# LOCO-WIFI.net
KiCad netlist of a schematic drawn in EAGLE
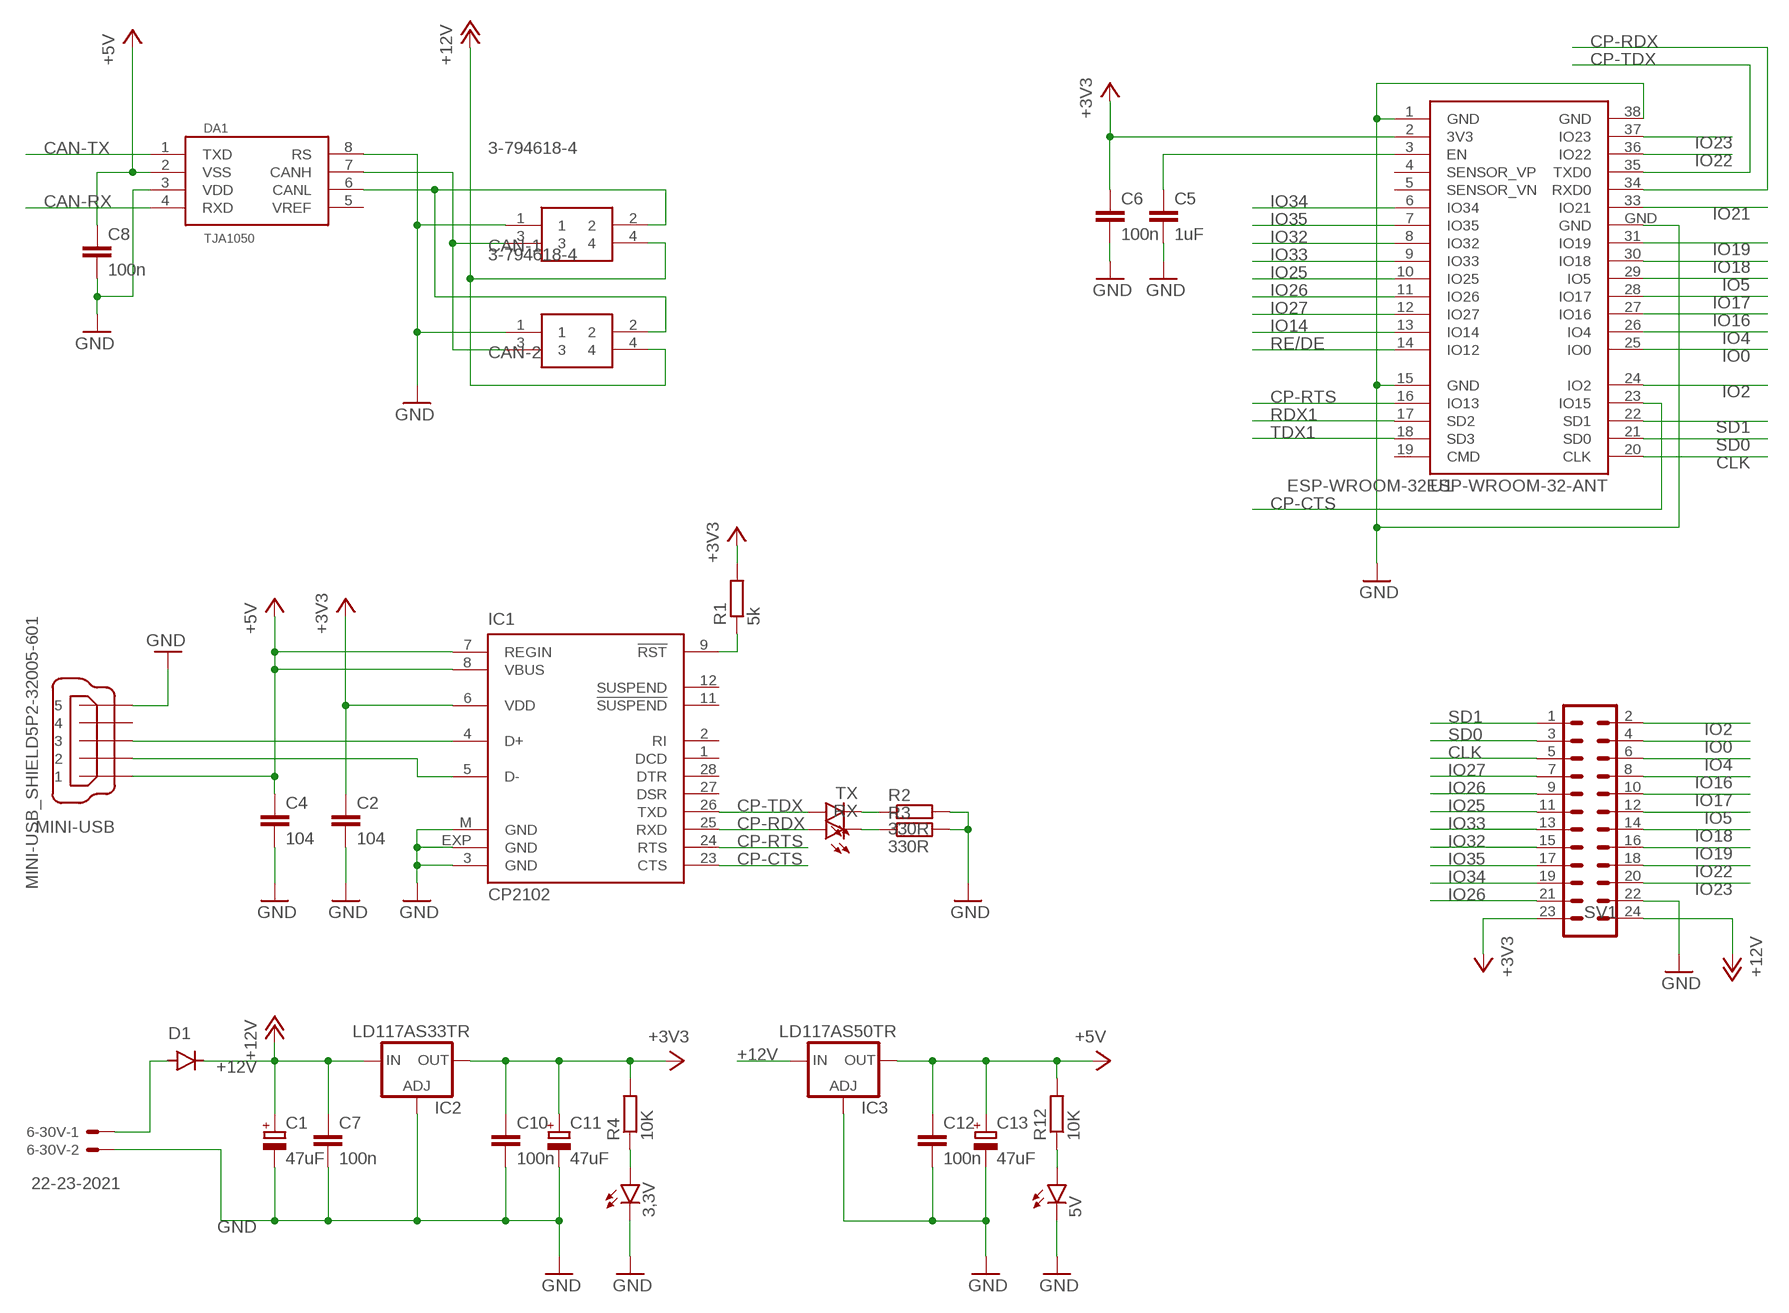
[diagram p0: schematic, sheet 1]

(export (version "E")
  (design (tool "Eeschema 10.0.6"))
  (components
    (comp (ref "3,3V")
      (value "LEDCHIPLED_0603")
      (footprint "eagle-import:CHIPLED_0603")
      (libsource (lib "eagle-import") (part "LEDCHIPLED_0603"))
    )
    (comp (ref "5V")
      (value "LEDCHIPLED_0603")
      (footprint "eagle-import:CHIPLED_0603")
      (libsource (lib "eagle-import") (part "LEDCHIPLED_0603"))
    )
    (comp (ref "6-30V")
      (value "22-23-2021")
      (footprint "eagle-import:22-23-2021")
      (fields (field (name "MF") "MOLEX"))
      (libsource (lib "eagle-import") (part "22-23-2021"))
    )
    (comp (ref "C1")
      (value "47uF")
      (footprint "eagle-import:B_3528-21R")
      (libsource (lib "eagle-import") (part "CPOL-EUB/3528-21R"))
    )
    (comp (ref "C2")
      (value "104")
      (footprint "eagle-import:C0402")
      (libsource (lib "eagle-import") (part "C-EUC0402"))
    )
    (comp (ref "C4")
      (value "104")
      (footprint "eagle-import:C0402")
      (libsource (lib "eagle-import") (part "C-EUC0402"))
    )
    (comp (ref "C5")
      (value "1uF")
      (footprint "eagle-import:C0402")
      (libsource (lib "eagle-import") (part "C-EUC0402"))
    )
    (comp (ref "C6")
      (value "100n")
      (footprint "eagle-import:C0402")
      (libsource (lib "eagle-import") (part "C-EUC0402"))
    )
    (comp (ref "C7")
      (value "100n")
      (footprint "eagle-import:C0402")
      (libsource (lib "eagle-import") (part "C-EUC0402"))
    )
    (comp (ref "C8")
      (value "100n")
      (footprint "eagle-import:C0402")
      (libsource (lib "eagle-import") (part "C-EUC0402"))
    )
    (comp (ref "C10")
      (value "100n")
      (footprint "eagle-import:C0402")
      (libsource (lib "eagle-import") (part "C-EUC0402"))
    )
    (comp (ref "C11")
      (value "47uF")
      (footprint "eagle-import:B_3528-21R")
      (libsource (lib "eagle-import") (part "CPOL-EUB/3528-21R"))
    )
    (comp (ref "C12")
      (value "100n")
      (footprint "eagle-import:C0402")
      (libsource (lib "eagle-import") (part "C-EUC0402"))
    )
    (comp (ref "C13")
      (value "47uF")
      (footprint "eagle-import:B_3528-21R")
      (libsource (lib "eagle-import") (part "CPOL-EUB/3528-21R"))
    )
    (comp (ref "CAN-1")
      (value "3-794618-4")
      (footprint "eagle-import:SHDRRA4W102P300_2X2_686X892X73")
      (libsource (lib "eagle-import") (part "3-794618-4"))
    )
    (comp (ref "CAN-2")
      (value "3-794618-4")
      (footprint "eagle-import:SHDRRA4W102P300_2X2_686X892X73")
      (libsource (lib "eagle-import") (part "3-794618-4"))
    )
    (comp (ref "D1")
      (value "DIODE-DO-214AC")
      (footprint "eagle-import:DO-214AC")
      (libsource (lib "eagle-import") (part "DIODE-DO-214AC"))
    )
    (comp (ref "DA1")
      (value "TJA1050")
      (footprint "eagle-import:SO08")
      (libsource (lib "eagle-import") (part "TJA1050"))
    )
    (comp (ref "IC1")
      (value "CP2102")
      (footprint "eagle-import:MLP28")
      (fields (field (name "MF") "FARNELL") (field (name "MPN") "CP2102-GM"))
      (libsource (lib "eagle-import") (part "CP2102"))
    )
    (comp (ref "IC2")
      (value "LD117AS33TR")
      (footprint "eagle-import:SOT223")
      (libsource (lib "eagle-import") (part "LD117A?S33TR"))
    )
    (comp (ref "IC3")
      (value "LD117AS50TR")
      (footprint "eagle-import:SOT223")
      (libsource (lib "eagle-import") (part "LD117A?S50TR"))
    )
    (comp (ref "MINI-USB")
      (value "MINI-USB_SHIELD5P2-32005-601")
      (footprint "eagle-import:32005-601")
      (libsource (lib "eagle-import") (part "MINI-USB_SHIELD5P2-32005-601"))
    )
    (comp (ref "R1")
      (value "5k")
      (footprint "eagle-import:R0603")
      (libsource (lib "eagle-import") (part "R-EU_R0603"))
    )
    (comp (ref "R2")
      (value "330R")
      (footprint "eagle-import:R0603")
      (libsource (lib "eagle-import") (part "R-EU_R0603"))
    )
    (comp (ref "R3")
      (value "330R")
      (footprint "eagle-import:R0603")
      (libsource (lib "eagle-import") (part "R-EU_R0603"))
    )
    (comp (ref "R4")
      (value "10K")
      (footprint "eagle-import:R0603")
      (libsource (lib "eagle-import") (part "R-EU_R0603"))
    )
    (comp (ref "R12")
      (value "10K")
      (footprint "eagle-import:R0603")
      (libsource (lib "eagle-import") (part "R-EU_R0603"))
    )
    (comp (ref "RX")
      (value "LEDCHIPLED_0603")
      (footprint "eagle-import:CHIPLED_0603")
      (libsource (lib "eagle-import") (part "LEDCHIPLED_0603"))
    )
    (comp (ref "SV1")
      (value "MA12-2")
      (footprint "eagle-import:MA12-2")
      (libsource (lib "eagle-import") (part "MA12-2"))
    )
    (comp (ref "TX")
      (value "LEDCHIPLED_0603")
      (footprint "eagle-import:CHIPLED_0603")
      (libsource (lib "eagle-import") (part "LEDCHIPLED_0603"))
    )
    (comp (ref "U1")
      (value "ESP-WROOM-32ESP-WROOM-32-ANT")
      (footprint "eagle-import:ESP-WROOM-32-ANT")
      (libsource (lib "eagle-import") (part "ESP-WROOM-32ESP-WROOM-32-ANT"))
    )
  )
  (nets
    (net (code "1") (name "+3V3") (class "Default")
      (node (ref "C10") (pin "1") (pinfunction "1_1") (pintype "passive"))
      (node (ref "C11") (pin "+") (pinfunction "+_+") (pintype "passive"))
      (node (ref "C2") (pin "1") (pinfunction "1_1") (pintype "passive"))
      (node (ref "C6") (pin "1") (pinfunction "1_1") (pintype "passive"))
      (node (ref "IC1") (pin "6") (pinfunction "VDD_6") (pintype "power_in"))
      (node (ref "IC2") (pin "4") (pinfunction "OUT_4") (pintype "passive"))
      (node (ref "R1") (pin "2") (pinfunction "2_2") (pintype "passive"))
      (node (ref "R4") (pin "2") (pinfunction "2_2") (pintype "passive"))
      (node (ref "SV1") (pin "23") (pinfunction "23_23") (pintype "passive"))
      (node (ref "U1") (pin "2") (pinfunction "3V3_2") (pintype "power_in"))
    )
    (net (code "2") (name "+5V") (class "Default")
      (node (ref "C12") (pin "1") (pinfunction "1_1") (pintype "passive"))
      (node (ref "C13") (pin "+") (pinfunction "+_+") (pintype "passive"))
      (node (ref "C4") (pin "1") (pinfunction "1_1") (pintype "passive"))
      (node (ref "C8") (pin "1") (pinfunction "1_1") (pintype "passive"))
      (node (ref "DA1") (pin "2") (pinfunction "VSS_2") (pintype "power_in"))
      (node (ref "IC1") (pin "7") (pinfunction "REGIN_7") (pintype "passive"))
      (node (ref "IC1") (pin "8") (pinfunction "VBUS_8") (pintype "input"))
      (node (ref "IC3") (pin "4") (pinfunction "OUT_4") (pintype "passive"))
      (node (ref "MINI-USB") (pin "1") (pinfunction "1_1") (pintype "passive"))
      (node (ref "R12") (pin "2") (pinfunction "2_2") (pintype "passive"))
    )
    (net (code "3") (name "+12V") (class "Default")
      (node (ref "C1") (pin "+") (pinfunction "+_+") (pintype "passive"))
      (node (ref "C7") (pin "1") (pinfunction "1_1") (pintype "passive"))
      (node (ref "CAN-1") (pin "4") (pinfunction "4_4") (pintype "bidirectional"))
      (node (ref "CAN-2") (pin "4") (pinfunction "4_4") (pintype "bidirectional"))
      (node (ref "D1") (pin "C") (pinfunction "C_C") (pintype "passive"))
      (node (ref "IC2") (pin "3") (pinfunction "IN_3") (pintype "input"))
      (node (ref "IC3") (pin "3") (pinfunction "IN_3") (pintype "input"))
      (node (ref "SV1") (pin "24") (pinfunction "24_24") (pintype "passive"))
    )
    (net (code "4") (name "/CAN-RX") (class "Default")
      (node (ref "DA1") (pin "4") (pinfunction "RXD_4") (pintype "output"))
    )
    (net (code "5") (name "/CAN-TX") (class "Default")
      (node (ref "DA1") (pin "1") (pinfunction "TXD_1") (pintype "input"))
    )
    (net (code "6") (name "/CLK") (class "Default")
      (node (ref "SV1") (pin "5") (pinfunction "5_5") (pintype "passive"))
      (node (ref "U1") (pin "20") (pinfunction "CLK_20") (pintype "bidirectional"))
    )
    (net (code "7") (name "/CP-CTS") (class "Default")
      (node (ref "IC1") (pin "23") (pinfunction "CTS_23") (pintype "input"))
      (node (ref "U1") (pin "23") (pinfunction "IO15_23") (pintype "bidirectional"))
    )
    (net (code "8") (name "/CP-RDX") (class "Default")
      (node (ref "IC1") (pin "25") (pinfunction "RXD_25") (pintype "input"))
      (node (ref "RX") (pin "A") (pinfunction "A_A") (pintype "passive"))
      (node (ref "U1") (pin "34") (pinfunction "RXD0_34") (pintype "bidirectional"))
    )
    (net (code "9") (name "/CP-RTS") (class "Default")
      (node (ref "IC1") (pin "24") (pinfunction "RTS_24") (pintype "output"))
      (node (ref "U1") (pin "16") (pinfunction "IO13_16") (pintype "bidirectional"))
    )
    (net (code "10") (name "/CP-TDX") (class "Default")
      (node (ref "IC1") (pin "26") (pinfunction "TXD_26") (pintype "output"))
      (node (ref "TX") (pin "A") (pinfunction "A_A") (pintype "passive"))
      (node (ref "U1") (pin "35") (pinfunction "TXD0_35") (pintype "bidirectional"))
    )
    (net (code "11") (name "/IO0") (class "Default")
      (node (ref "SV1") (pin "4") (pinfunction "4_4") (pintype "passive"))
      (node (ref "U1") (pin "25") (pinfunction "IO0_25") (pintype "bidirectional"))
    )
    (net (code "12") (name "/IO2") (class "Default")
      (node (ref "SV1") (pin "2") (pinfunction "2_2") (pintype "passive"))
      (node (ref "U1") (pin "24") (pinfunction "IO2_24") (pintype "bidirectional"))
    )
    (net (code "13") (name "/IO4") (class "Default")
      (node (ref "SV1") (pin "6") (pinfunction "6_6") (pintype "passive"))
      (node (ref "U1") (pin "26") (pinfunction "IO4_26") (pintype "bidirectional"))
    )
    (net (code "14") (name "/IO5") (class "Default")
      (node (ref "SV1") (pin "12") (pinfunction "12_12") (pintype "passive"))
      (node (ref "U1") (pin "29") (pinfunction "IO5_29") (pintype "bidirectional"))
    )
    (net (code "15") (name "/IO14") (class "Default")
      (node (ref "U1") (pin "13") (pinfunction "IO14_13") (pintype "bidirectional"))
    )
    (net (code "16") (name "/IO16") (class "Default")
      (node (ref "SV1") (pin "8") (pinfunction "8_8") (pintype "passive"))
      (node (ref "U1") (pin "27") (pinfunction "IO16_27") (pintype "bidirectional"))
    )
    (net (code "17") (name "/IO17") (class "Default")
      (node (ref "SV1") (pin "10") (pinfunction "10_10") (pintype "passive"))
      (node (ref "U1") (pin "28") (pinfunction "IO17_28") (pintype "bidirectional"))
    )
    (net (code "18") (name "/IO18") (class "Default")
      (node (ref "SV1") (pin "14") (pinfunction "14_14") (pintype "passive"))
      (node (ref "U1") (pin "30") (pinfunction "IO18_30") (pintype "bidirectional"))
    )
    (net (code "19") (name "/IO19") (class "Default")
      (node (ref "SV1") (pin "16") (pinfunction "16_16") (pintype "passive"))
      (node (ref "U1") (pin "31") (pinfunction "IO19_31") (pintype "bidirectional"))
    )
    (net (code "20") (name "/IO21") (class "Default")
      (node (ref "U1") (pin "33") (pinfunction "IO21_33") (pintype "bidirectional"))
    )
    (net (code "21") (name "/IO22") (class "Default")
      (node (ref "SV1") (pin "18") (pinfunction "18_18") (pintype "passive"))
      (node (ref "U1") (pin "36") (pinfunction "IO22_36") (pintype "bidirectional"))
    )
    (net (code "22") (name "/IO23") (class "Default")
      (node (ref "SV1") (pin "20") (pinfunction "20_20") (pintype "passive"))
      (node (ref "U1") (pin "37") (pinfunction "IO23_37") (pintype "bidirectional"))
    )
    (net (code "23") (name "/IO25") (class "Default")
      (node (ref "SV1") (pin "11") (pinfunction "11_11") (pintype "passive"))
      (node (ref "U1") (pin "10") (pinfunction "IO25_10") (pintype "bidirectional"))
    )
    (net (code "24") (name "/IO26") (class "Default")
      (node (ref "SV1") (pin "21") (pinfunction "21_21") (pintype "passive"))
      (node (ref "SV1") (pin "9") (pinfunction "9_9") (pintype "passive"))
      (node (ref "U1") (pin "11") (pinfunction "IO26_11") (pintype "bidirectional"))
    )
    (net (code "25") (name "/IO27") (class "Default")
      (node (ref "SV1") (pin "7") (pinfunction "7_7") (pintype "passive"))
      (node (ref "U1") (pin "12") (pinfunction "IO27_12") (pintype "bidirectional"))
    )
    (net (code "26") (name "/IO32") (class "Default")
      (node (ref "SV1") (pin "15") (pinfunction "15_15") (pintype "passive"))
      (node (ref "U1") (pin "8") (pinfunction "IO32_8") (pintype "bidirectional"))
    )
    (net (code "27") (name "/IO33") (class "Default")
      (node (ref "SV1") (pin "13") (pinfunction "13_13") (pintype "passive"))
      (node (ref "U1") (pin "9") (pinfunction "IO33_9") (pintype "bidirectional"))
    )
    (net (code "28") (name "/IO34") (class "Default")
      (node (ref "SV1") (pin "19") (pinfunction "19_19") (pintype "passive"))
      (node (ref "U1") (pin "6") (pinfunction "IO34_6") (pintype "bidirectional"))
    )
    (net (code "29") (name "/IO35") (class "Default")
      (node (ref "SV1") (pin "17") (pinfunction "17_17") (pintype "passive"))
      (node (ref "U1") (pin "7") (pinfunction "IO35_7") (pintype "bidirectional"))
    )
    (net (code "30") (name "/RDX1") (class "Default")
      (node (ref "U1") (pin "17") (pinfunction "SD2_17") (pintype "bidirectional"))
    )
    (net (code "31") (name "/RE{slash}DE") (class "Default")
      (node (ref "U1") (pin "14") (pinfunction "IO12_14") (pintype "bidirectional"))
    )
    (net (code "32") (name "/SD0") (class "Default")
      (node (ref "SV1") (pin "3") (pinfunction "3_3") (pintype "passive"))
      (node (ref "U1") (pin "21") (pinfunction "SD0_21") (pintype "bidirectional"))
    )
    (net (code "33") (name "/SD1") (class "Default")
      (node (ref "SV1") (pin "1") (pinfunction "1_1") (pintype "passive"))
      (node (ref "U1") (pin "22") (pinfunction "SD1_22") (pintype "bidirectional"))
    )
    (net (code "34") (name "/TDX1") (class "Default")
      (node (ref "U1") (pin "18") (pinfunction "SD3_18") (pintype "bidirectional"))
    )
    (net (code "35") (name "GND") (class "Default")
      (node (ref "3,3V") (pin "C") (pinfunction "C_C") (pintype "passive"))
      (node (ref "5V") (pin "C") (pinfunction "C_C") (pintype "passive"))
      (node (ref "6-30V") (pin "2") (pinfunction "S_2") (pintype "passive"))
      (node (ref "C1") (pin "-") (pinfunction "-_-") (pintype "passive"))
      (node (ref "C10") (pin "2") (pinfunction "2_2") (pintype "passive"))
      (node (ref "C11") (pin "-") (pinfunction "-_-") (pintype "passive"))
      (node (ref "C12") (pin "2") (pinfunction "2_2") (pintype "passive"))
      (node (ref "C13") (pin "-") (pinfunction "-_-") (pintype "passive"))
      (node (ref "C2") (pin "2") (pinfunction "2_2") (pintype "passive"))
      (node (ref "C4") (pin "2") (pinfunction "2_2") (pintype "passive"))
      (node (ref "C5") (pin "2") (pinfunction "2_2") (pintype "passive"))
      (node (ref "C6") (pin "2") (pinfunction "2_2") (pintype "passive"))
      (node (ref "C7") (pin "2") (pinfunction "2_2") (pintype "passive"))
      (node (ref "C8") (pin "2") (pinfunction "2_2") (pintype "passive"))
      (node (ref "CAN-1") (pin "1") (pinfunction "1_1") (pintype "bidirectional"))
      (node (ref "CAN-2") (pin "1") (pinfunction "1_1") (pintype "bidirectional"))
      (node (ref "DA1") (pin "3") (pinfunction "VDD_3") (pintype "power_in"))
      (node (ref "DA1") (pin "8") (pinfunction "RS_8") (pintype "input"))
      (node (ref "IC1") (pin "3") (pinfunction "GND_3") (pintype "power_in"))
      (node (ref "IC1") (pin "EXP") (pinfunction "GND_EXP") (pintype "power_in"))
      (node (ref "IC1") (pin "M") (pinfunction "GND_M") (pintype "power_in"))
      (node (ref "IC2") (pin "1") (pinfunction "ADJ_1") (pintype "input"))
      (node (ref "IC3") (pin "1") (pinfunction "ADJ_1") (pintype "input"))
      (node (ref "MINI-USB") (pin "5") (pinfunction "5_5") (pintype "passive"))
      (node (ref "R2") (pin "2") (pinfunction "2_2") (pintype "passive"))
      (node (ref "R3") (pin "2") (pinfunction "2_2") (pintype "passive"))
      (node (ref "SV1") (pin "22") (pinfunction "22_22") (pintype "passive"))
      (node (ref "U1") (pin "1") (pinfunction "GND_1") (pintype "power_in"))
      (node (ref "U1") (pin "15") (pinfunction "GND_15") (pintype "power_in"))
      (node (ref "U1") (pin "38") (pinfunction "GND_38") (pintype "power_in"))
      (node (ref "U1") (pin "GND") (pinfunction "GND_GND") (pintype "power_in"))
    )
    (net (code "36") (name "Net-(3,3V-PadA)") (class "Default")
      (node (ref "3,3V") (pin "A") (pinfunction "A_A") (pintype "passive"))
      (node (ref "R4") (pin "1") (pinfunction "1_1") (pintype "passive"))
    )
    (net (code "37") (name "Net-(5V-PadA)") (class "Default")
      (node (ref "5V") (pin "A") (pinfunction "A_A") (pintype "passive"))
      (node (ref "R12") (pin "1") (pinfunction "1_1") (pintype "passive"))
    )
    (net (code "38") (name "Net-(6-30VA-S)") (class "Default")
      (node (ref "6-30V") (pin "1") (pinfunction "S_1") (pintype "passive"))
      (node (ref "D1") (pin "A") (pinfunction "A_A") (pintype "passive"))
    )
    (net (code "39") (name "Net-(DA1-CANH)") (class "Default")
      (node (ref "CAN-1") (pin "3") (pinfunction "3_3") (pintype "bidirectional"))
      (node (ref "CAN-2") (pin "3") (pinfunction "3_3") (pintype "bidirectional"))
      (node (ref "DA1") (pin "7") (pinfunction "CANH_7") (pintype "bidirectional"))
    )
    (net (code "40") (name "Net-(DA1-CANL)") (class "Default")
      (node (ref "CAN-1") (pin "2") (pinfunction "2_2") (pintype "bidirectional"))
      (node (ref "CAN-2") (pin "2") (pinfunction "2_2") (pintype "bidirectional"))
      (node (ref "DA1") (pin "6") (pinfunction "CANL_6") (pintype "bidirectional"))
    )
    (net (code "41") (name "Net-(IC1-D+)") (class "Default")
      (node (ref "IC1") (pin "4") (pinfunction "D+_4") (pintype "bidirectional"))
      (node (ref "MINI-USB") (pin "3") (pinfunction "3_3") (pintype "passive"))
    )
    (net (code "42") (name "Net-(IC1-D-)") (class "Default")
      (node (ref "IC1") (pin "5") (pinfunction "D-_5") (pintype "bidirectional"))
      (node (ref "MINI-USB") (pin "2") (pinfunction "2_2") (pintype "passive"))
    )
    (net (code "43") (name "Net-(IC1-~{RST})") (class "Default")
      (node (ref "IC1") (pin "9") (pinfunction "~{RST}_9") (pintype "bidirectional"))
      (node (ref "R1") (pin "1") (pinfunction "1_1") (pintype "passive"))
    )
    (net (code "44") (name "Net-(R2-Pad1)") (class "Default")
      (node (ref "R2") (pin "1") (pinfunction "1_1") (pintype "passive"))
      (node (ref "TX") (pin "C") (pinfunction "C_C") (pintype "passive"))
    )
    (net (code "45") (name "Net-(R3-Pad1)") (class "Default")
      (node (ref "R3") (pin "1") (pinfunction "1_1") (pintype "passive"))
      (node (ref "RX") (pin "C") (pinfunction "C_C") (pintype "passive"))
    )
    (net (code "46") (name "Net-(U1-EN)") (class "Default")
      (node (ref "C5") (pin "1") (pinfunction "1_1") (pintype "passive"))
      (node (ref "U1") (pin "3") (pinfunction "EN_3") (pintype "input"))
    )
    (net (code "47") (name "unconnected-(DA1-VREF-Pad5)") (class "Default")
      (node (ref "DA1") (pin "5") (pinfunction "VREF_5") (pintype "passive"))
    )
    (net (code "48") (name "unconnected-(IC1-DCD-Pad1)") (class "Default")
      (node (ref "IC1") (pin "1") (pinfunction "DCD_1") (pintype "input"))
    )
    (net (code "49") (name "unconnected-(IC1-DSR-Pad27)") (class "Default")
      (node (ref "IC1") (pin "27") (pinfunction "DSR_27") (pintype "input"))
    )
    (net (code "50") (name "unconnected-(IC1-DTR-Pad28)") (class "Default")
      (node (ref "IC1") (pin "28") (pinfunction "DTR_28") (pintype "output"))
    )
    (net (code "51") (name "unconnected-(IC1-RI-Pad2)") (class "Default")
      (node (ref "IC1") (pin "2") (pinfunction "RI_2") (pintype "input"))
    )
    (net (code "52") (name "unconnected-(IC1-SUSPEND-Pad12)") (class "Default")
      (node (ref "IC1") (pin "12") (pinfunction "SUSPEND_12") (pintype "output"))
    )
    (net (code "53") (name "unconnected-(IC1-~{SUSPEND}-Pad11)") (class "Default")
      (node (ref "IC1") (pin "11") (pinfunction "~{SUSPEND}_11") (pintype "output"))
    )
    (net (code "54") (name "unconnected-(MINI-USB-Pad4)") (class "Default")
      (node (ref "MINI-USB") (pin "4") (pinfunction "4_4") (pintype "passive"))
    )
    (net (code "55") (name "unconnected-(U1-CMD-Pad19)") (class "Default")
      (node (ref "U1") (pin "19") (pinfunction "CMD_19") (pintype "bidirectional"))
    )
    (net (code "56") (name "unconnected-(U1-SENSOR_VN-Pad5)") (class "Default")
      (node (ref "U1") (pin "5") (pinfunction "SENSOR_VN_5") (pintype "bidirectional"))
    )
    (net (code "57") (name "unconnected-(U1-SENSOR_VP-Pad4)") (class "Default")
      (node (ref "U1") (pin "4") (pinfunction "SENSOR_VP_4") (pintype "bidirectional"))
    )
  )
)
